# Filter_Amp_Circuit.net
KiCad netlist of a schematic drawn in EAGLE
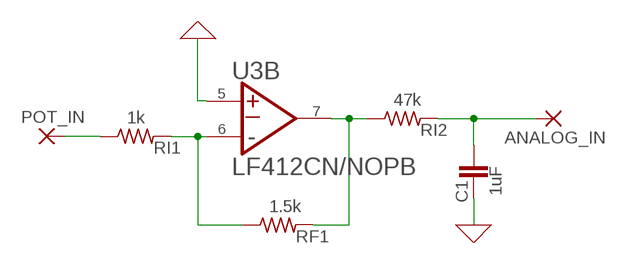
[diagram p0: schematic, sheet 1]

(export (version "E")
  (design (tool "Eeschema 10.0.6"))
  (components
    (comp (ref "ANALOG_IN")
      (value "1,6/0,8")
      (footprint "eagle-import:1,6_0,8")
      (libsource (lib "eagle-import") (part "1,6/0,8"))
    )
    (comp (ref "C1")
      (value "1uF")
      (footprint "eagle-import:C2.5-3")
      (libsource (lib "eagle-import") (part "C2,5-3"))
    )
    (comp (ref "POT_IN")
      (value "1,6/0,8")
      (footprint "eagle-import:1,6_0,8")
      (libsource (lib "eagle-import") (part "1,6/0,8"))
    )
    (comp (ref "RF1")
      (value "1.5k")
      (footprint "eagle-import:0309_10")
      (libsource (lib "eagle-import") (part "R-US_0309/10"))
    )
    (comp (ref "RI1")
      (value "1k")
      (footprint "eagle-import:0309_10")
      (libsource (lib "eagle-import") (part "R-US_0309/10"))
    )
    (comp (ref "RI2")
      (value "47k")
      (footprint "eagle-import:0309_10")
      (libsource (lib "eagle-import") (part "R-US_0309/10"))
    )
    (comp (ref "U3")
      (value "TEXAS_INSTRUMENTS_LF412CN-NOPBTEXAS_INSTRUMENTS_LF412CN-NOPB_0_0")
      (footprint "eagle-import:TEXAS_INSTRUMENTS_LF412CN-NOPB_0")
      (fields
        (field (name "DIGIKEY_PART_NUMBER") "LF412CN/NOPB-ND")
        (field (name "MF") "Texas Instruments")
        (field (name "MOUSER_PART_NUMBER") "926-LF412CN/NOPB")
      )
      (libsource (lib "eagle-import") (part "TEXAS_INSTRUMENTS_LF412CN-NOPBTEXAS_INSTRUMENTS_LF412CN-NOPB_0_0"))
    )
  )
  (nets
    (net (code "1") (name "GND") (class "Default")
      (node (ref "C1") (pin "2") (pinfunction "2_2") (pintype "passive"))
      (node (ref "U3") (pin "5") (pinfunction "NON-INVERTING_INPUT_B_5") (pintype "tri_state"))
    )
    (net (code "2") (name "Net-(ANALOG_IN-P)") (class "Default")
      (node (ref "ANALOG_IN") (pin "1") (pinfunction "P_1") (pintype "passive"))
      (node (ref "C1") (pin "1") (pinfunction "1_1") (pintype "passive"))
      (node (ref "RI2") (pin "2") (pinfunction "2_2") (pintype "passive"))
    )
    (net (code "3") (name "Net-(POT_IN-P)") (class "Default")
      (node (ref "POT_IN") (pin "1") (pinfunction "P_1") (pintype "passive"))
      (node (ref "RI1") (pin "1") (pinfunction "1_1") (pintype "passive"))
    )
    (net (code "4") (name "Net-(U3B-INVERTING_INPUT_B)") (class "Default")
      (node (ref "RF1") (pin "1") (pinfunction "1_1") (pintype "passive"))
      (node (ref "RI1") (pin "2") (pinfunction "2_2") (pintype "passive"))
      (node (ref "U3") (pin "6") (pinfunction "INVERTING_INPUT_B_6") (pintype "tri_state"))
    )
    (net (code "5") (name "Net-(U3B-OUTPUT_B)") (class "Default")
      (node (ref "RF1") (pin "2") (pinfunction "2_2") (pintype "passive"))
      (node (ref "RI2") (pin "1") (pinfunction "1_1") (pintype "passive"))
      (node (ref "U3") (pin "7") (pinfunction "OUTPUT_B_7") (pintype "passive"))
    )
  )
)
